# DAC.net
KiCad netlist of a schematic drawn in Altium Designer
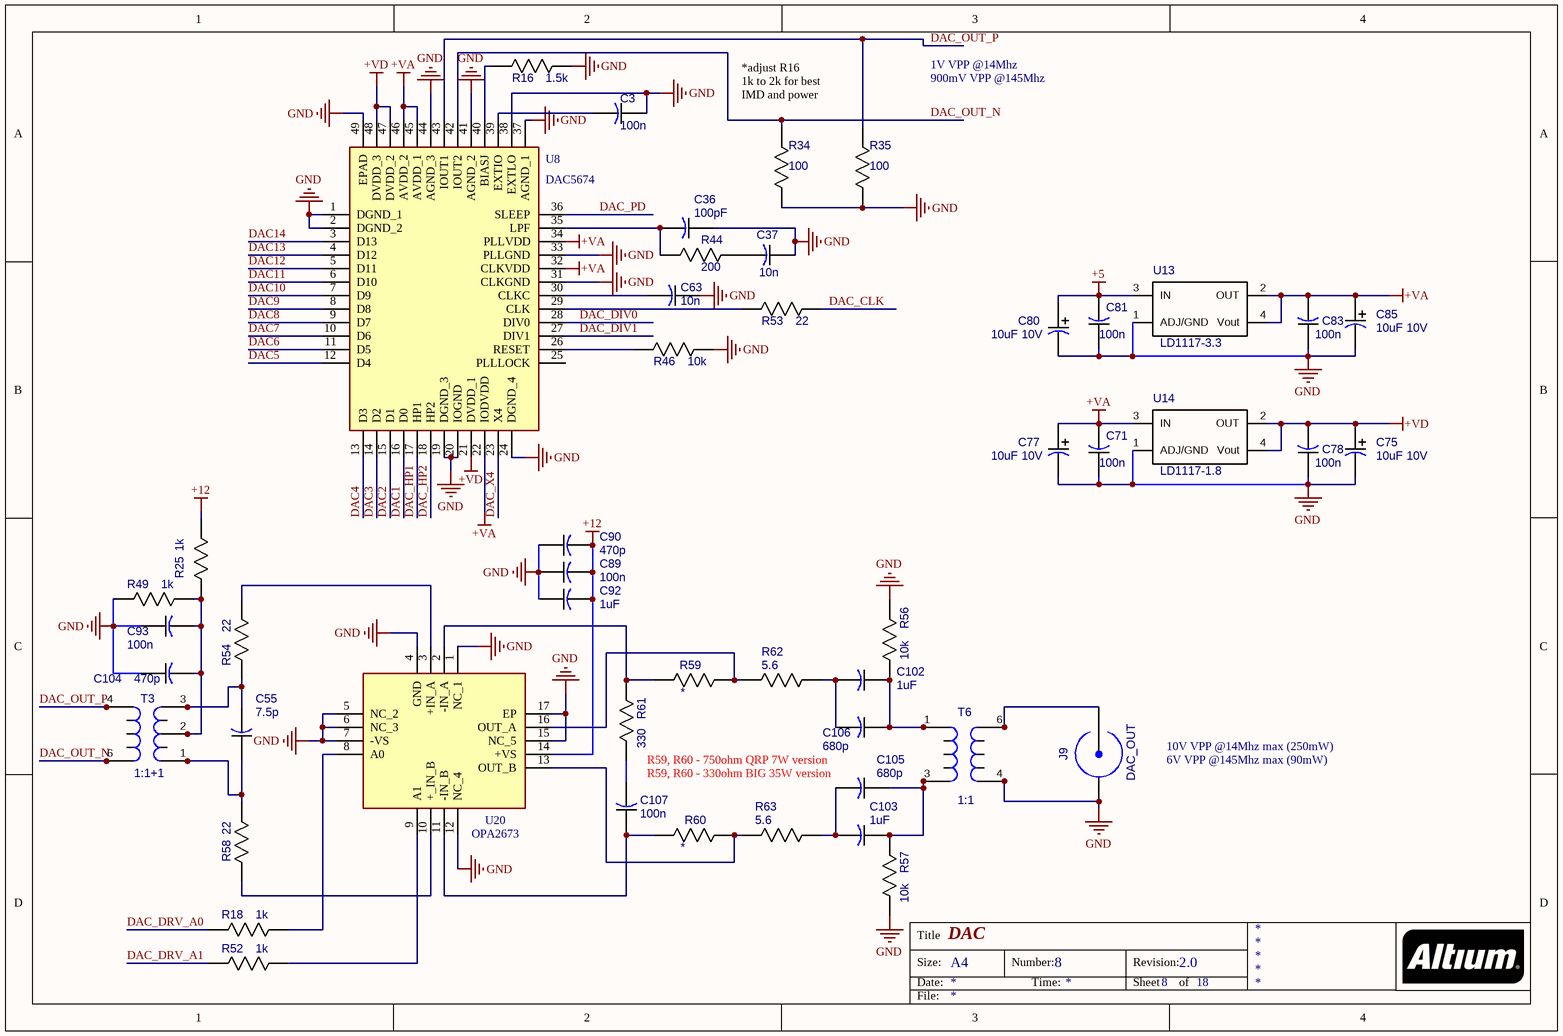
[diagram p0: DAC.SchDoc]

(export (version "E")
  (design (tool "Eeschema 10.0.6"))
  (components
    (comp (ref "C3")
      (value "100n")
      (footprint "CAP_0805")
      (description "CAP_0805")
      (libsource (lib "*") (part "CAP_0805"))
    )
    (comp (ref "C36")
      (value "100pF")
      (footprint "CAP_0805")
      (description "CAP_0805")
      (libsource (lib "*") (part "CAP_0805"))
    )
    (comp (ref "C37")
      (value "10n")
      (footprint "CAP_0805")
      (description "CAP_0805")
      (libsource (lib "*") (part "CAP_0805"))
    )
    (comp (ref "C55")
      (value "7.5p")
      (footprint "CAP_0805")
      (description "CAP_0805")
      (libsource (lib "*") (part "CAP_0805"))
    )
    (comp (ref "C63")
      (value "10n")
      (footprint "CAP_0805")
      (description "CAP_0805")
      (libsource (lib "*") (part "CAP_0805"))
    )
    (comp (ref "C71")
      (value "100n")
      (footprint "CAP_0805")
      (description "CAP_0805")
      (libsource (lib "*") (part "CAP_0805"))
    )
    (comp (ref "C75")
      (value "10uF 10V")
      (footprint "CAPAE_4.3x4.3h5.4")
      (description "CAPAE_4.3x4.3h5.4")
      (libsource (lib "MOTHERBOARD") (part "CAPAE_4.3x4.3h5.4"))
    )
    (comp (ref "C77")
      (value "10uF 10V")
      (footprint "CAPAE_4.3x4.3h5.4")
      (description "CAPAE_4.3x4.3h5.4")
      (libsource (lib "MOTHERBOARD") (part "CAPAE_4.3x4.3h5.4"))
    )
    (comp (ref "C78")
      (value "100n")
      (footprint "CAP_0805")
      (description "CAP_0805")
      (libsource (lib "*") (part "CAP_0805"))
    )
    (comp (ref "C80")
      (value "10uF 10V")
      (footprint "CAPAE_4.3x4.3h5.4")
      (description "CAPAE_4.3x4.3h5.4")
      (libsource (lib "MOTHERBOARD") (part "CAPAE_4.3x4.3h5.4"))
    )
    (comp (ref "C81")
      (value "100n")
      (footprint "CAP_0805")
      (description "CAP_0805")
      (libsource (lib "*") (part "CAP_0805"))
    )
    (comp (ref "C83")
      (value "100n")
      (footprint "CAP_0805")
      (description "CAP_0805")
      (libsource (lib "*") (part "CAP_0805"))
    )
    (comp (ref "C85")
      (value "10uF 10V")
      (footprint "CAPAE_4.3x4.3h5.4")
      (description "CAPAE_4.3x4.3h5.4")
      (libsource (lib "MOTHERBOARD") (part "CAPAE_4.3x4.3h5.4"))
    )
    (comp (ref "C89")
      (value "100n")
      (footprint "CAP_0805")
      (description "CAP_0805")
      (libsource (lib "*") (part "CAP_0805"))
    )
    (comp (ref "C90")
      (value "470p")
      (footprint "CAP_0805")
      (description "CAP_0805")
      (libsource (lib "*") (part "CAP_0805"))
    )
    (comp (ref "C92")
      (value "1uF")
      (footprint "CAP_0805")
      (description "CAP_0805")
      (libsource (lib "*") (part "CAP_0805"))
    )
    (comp (ref "C93")
      (value "100n")
      (footprint "CAP_0805")
      (description "CAP_0805")
      (libsource (lib "*") (part "CAP_0805"))
    )
    (comp (ref "C102")
      (value "1uF")
      (footprint "CAP_1206")
      (description "CAP_1206")
      (libsource (lib "*") (part "CAP_1206"))
    )
    (comp (ref "C103")
      (value "1uF")
      (footprint "CAP_1206")
      (description "CAP_1206")
      (libsource (lib "*") (part "CAP_1206"))
    )
    (comp (ref "C104")
      (value "470p")
      (footprint "CAP_0805")
      (description "CAP_0805")
      (libsource (lib "*") (part "CAP_0805"))
    )
    (comp (ref "C105")
      (value "680p")
      (footprint "CAP_1206")
      (description "CAP_1206")
      (libsource (lib "*") (part "CAP_1206"))
    )
    (comp (ref "C106")
      (value "680p")
      (footprint "CAP_1206")
      (description "CAP_1206")
      (libsource (lib "*") (part "CAP_1206"))
    )
    (comp (ref "C107")
      (value "100n")
      (footprint "CAP_0805")
      (description "CAP_0805")
      (libsource (lib "*") (part "CAP_0805"))
    )
    (comp (ref "J9")
      (value "DAC_OUT")
      (footprint "31-5431")
      (description "SMA")
      (libsource (lib "RF-UNIT_1") (part "31-5431"))
    )
    (comp (ref "R16")
      (value "1.5k")
      (footprint "RES_0805")
      (description "RES_0805")
      (libsource (lib "*") (part "RES_0805"))
    )
    (comp (ref "R18")
      (value "1k")
      (footprint "RES_0805")
      (description "RES_0805")
      (libsource (lib "*") (part "RES_0805"))
    )
    (comp (ref "R25")
      (value "1k")
      (footprint "RES_0805")
      (description "RES_0805")
      (libsource (lib "*") (part "RES_0805"))
    )
    (comp (ref "R34")
      (value "100")
      (footprint "RES_0805")
      (description "RES_0805")
      (libsource (lib "*") (part "RES_0805"))
    )
    (comp (ref "R35")
      (value "100")
      (footprint "RES_0805")
      (description "RES_0805")
      (libsource (lib "*") (part "RES_0805"))
    )
    (comp (ref "R44")
      (value "200")
      (footprint "RES_0805")
      (description "RES_0805")
      (libsource (lib "*") (part "RES_0805"))
    )
    (comp (ref "R46")
      (value "10k")
      (footprint "RES_0805")
      (description "RES_0805")
      (libsource (lib "*") (part "RES_0805"))
    )
    (comp (ref "R49")
      (value "1k")
      (footprint "RES_0805")
      (description "RES_0805")
      (libsource (lib "*") (part "RES_0805"))
    )
    (comp (ref "R52")
      (value "1k")
      (footprint "RES_0805")
      (description "RES_0805")
      (libsource (lib "*") (part "RES_0805"))
    )
    (comp (ref "R53")
      (value "22")
      (footprint "RES_0805")
      (description "RES_0805")
      (libsource (lib "*") (part "RES_0805"))
    )
    (comp (ref "R54")
      (value "22")
      (footprint "RES_0805")
      (description "RES_0805")
      (libsource (lib "*") (part "RES_0805"))
    )
    (comp (ref "R56")
      (value "10k")
      (footprint "RES_0805")
      (description "RES_0805")
      (libsource (lib "*") (part "RES_0805"))
    )
    (comp (ref "R57")
      (value "10k")
      (footprint "RES_0805")
      (description "RES_0805")
      (libsource (lib "*") (part "RES_0805"))
    )
    (comp (ref "R58")
      (value "22")
      (footprint "RES_0805")
      (description "RES_0805")
      (libsource (lib "*") (part "RES_0805"))
    )
    (comp (ref "R59")
      (value "*")
      (footprint "RES_0805")
      (description "RES_0805")
      (libsource (lib "*") (part "RES_0805"))
    )
    (comp (ref "R60")
      (value "*")
      (footprint "RES_0805")
      (description "RES_0805")
      (libsource (lib "*") (part "RES_0805"))
    )
    (comp (ref "R61")
      (value "330")
      (footprint "RES_0805")
      (description "RES_0805")
      (libsource (lib "*") (part "RES_0805"))
    )
    (comp (ref "R62")
      (value "5.6")
      (footprint "RES_1206")
      (description "RES_1206")
      (libsource (lib "*") (part "RES_1206"))
    )
    (comp (ref "R63")
      (value "5.6")
      (footprint "RES_1206")
      (description "RES_1206")
      (libsource (lib "*") (part "RES_1206"))
    )
    (comp (ref "T3")
      (value "1:1+1")
      (footprint "TRANSF_ACORE2")
      (description "Transformer")
      (libsource (lib "MOTHERBOARD_1") (part "TRANSF_ACORE2"))
    )
    (comp (ref "T6")
      (value "1:1")
      (footprint "TRANSF_ACORE")
      (description "Transformer")
      (libsource (lib "MOTHERBOARD_1") (part "TRANSF_ACORE"))
    )
    (comp (ref "U8")
      (value "DAC5674")
      (footprint "SamacSys:QFP50P900X900X100-49N")
      (description "Integrated Circuit")
      (fields (field (name "MANUFACTURER_PART_NUMBER") "DAC5674IPHP"))
      (libsource (lib "*") (part "DAC5674IPHP"))
    )
    (comp (ref "U13")
      (value "LD1117-3.3")
      (footprint "LT1117CST-3.3")
      (description "LT1117CST-3.3")
      (fields (field (name "Comment") "1117-3.3"))
      (libsource (lib "*") (part "LT1117CST-3.3"))
    )
    (comp (ref "U14")
      (value "LD1117-1.8")
      (footprint "LT1117CST-3.3")
      (description "LT1117CST-1.8")
      (fields (field (name "Comment") "1117-1.8"))
      (libsource (lib "*") (part "LT1117CST-3.3"))
    )
    (comp (ref "U20")
      (value "OPA2673")
      (footprint "SamacSys:QFN65P400X400X100-17N-D")
      (description "Integrated Circuit")
      (fields
        (field (name "MANUFACTURER_PART_NUMBER") "OPA2673IRGVT")
        (field (name "MOUSER PART NUMBER") "595-OPA2673IRGVT")
      )
      (libsource (lib "*") (part "OPA2673IRGVT"))
    )
  )
  (nets
    (net (code "1") (name "+5") (class "Default")
      (node (ref "C80") (pin "1") (pinfunction "PLUS_1") (pintype "passive"))
      (node (ref "C81") (pin "2") (pinfunction "2_2") (pintype "passive"))
      (node (ref "U13") (pin "3") (pinfunction "IN_3") (pintype "passive"))
    )
    (net (code "2") (name "+12") (class "Default")
      (node (ref "C89") (pin "2") (pinfunction "2_2") (pintype "passive"))
      (node (ref "C90") (pin "2") (pinfunction "2_2") (pintype "passive"))
      (node (ref "C92") (pin "2") (pinfunction "2_2") (pintype "passive"))
      (node (ref "R25") (pin "2") (pinfunction "2_2") (pintype "passive"))
      (node (ref "U20") (pin "14") (pinfunction "+VS_14") (pintype "passive"))
    )
    (net (code "3") (name "+VA") (class "Default")
      (node (ref "C71") (pin "2") (pinfunction "2_2") (pintype "passive"))
      (node (ref "C77") (pin "1") (pinfunction "PLUS_1") (pintype "passive"))
      (node (ref "C83") (pin "2") (pinfunction "2_2") (pintype "passive"))
      (node (ref "C85") (pin "1") (pinfunction "PLUS_1") (pintype "passive"))
      (node (ref "U13") (pin "2") (pinfunction "OUT_2") (pintype "passive"))
      (node (ref "U13") (pin "4") (pinfunction "Vout_4") (pintype "passive"))
      (node (ref "U14") (pin "3") (pinfunction "IN_3") (pintype "passive"))
      (node (ref "U8") (pin "22") (pinfunction "IODVDD_22") (pintype "passive"))
      (node (ref "U8") (pin "32") (pinfunction "CLKVDD_32") (pintype "passive"))
      (node (ref "U8") (pin "34") (pinfunction "PLLVDD_34") (pintype "passive"))
      (node (ref "U8") (pin "45") (pinfunction "AVDD_1_45") (pintype "passive"))
      (node (ref "U8") (pin "46") (pinfunction "AVDD_2_46") (pintype "passive"))
    )
    (net (code "4") (name "+VD") (class "Default")
      (node (ref "C75") (pin "1") (pinfunction "PLUS_1") (pintype "passive"))
      (node (ref "C78") (pin "2") (pinfunction "2_2") (pintype "passive"))
      (node (ref "U14") (pin "2") (pinfunction "OUT_2") (pintype "passive"))
      (node (ref "U14") (pin "4") (pinfunction "Vout_4") (pintype "passive"))
      (node (ref "U8") (pin "21") (pinfunction "DVDD_1_21") (pintype "passive"))
      (node (ref "U8") (pin "47") (pinfunction "DVDD_2_47") (pintype "passive"))
      (node (ref "U8") (pin "48") (pinfunction "DVDD_3_48") (pintype "passive"))
    )
    (net (code "5") (name "/DAC1") (class "Default")
      (node (ref "U8") (pin "16") (pinfunction "D0_16") (pintype "passive"))
    )
    (net (code "6") (name "/DAC2") (class "Default")
      (node (ref "U8") (pin "15") (pinfunction "D1_15") (pintype "passive"))
    )
    (net (code "7") (name "/DAC3") (class "Default")
      (node (ref "U8") (pin "14") (pinfunction "D2_14") (pintype "passive"))
    )
    (net (code "8") (name "/DAC4") (class "Default")
      (node (ref "U8") (pin "13") (pinfunction "D3_13") (pintype "passive"))
    )
    (net (code "9") (name "/DAC5") (class "Default")
      (node (ref "U8") (pin "12") (pinfunction "D4_12") (pintype "passive"))
    )
    (net (code "10") (name "/DAC6") (class "Default")
      (node (ref "U8") (pin "11") (pinfunction "D5_11") (pintype "passive"))
    )
    (net (code "11") (name "/DAC7") (class "Default")
      (node (ref "U8") (pin "10") (pinfunction "D6_10") (pintype "passive"))
    )
    (net (code "12") (name "/DAC8") (class "Default")
      (node (ref "U8") (pin "9") (pinfunction "D7_9") (pintype "passive"))
    )
    (net (code "13") (name "/DAC9") (class "Default")
      (node (ref "U8") (pin "8") (pinfunction "D8_8") (pintype "passive"))
    )
    (net (code "14") (name "/DAC10") (class "Default")
      (node (ref "U8") (pin "7") (pinfunction "D9_7") (pintype "passive"))
    )
    (net (code "15") (name "/DAC11") (class "Default")
      (node (ref "U8") (pin "6") (pinfunction "D10_6") (pintype "passive"))
    )
    (net (code "16") (name "/DAC12") (class "Default")
      (node (ref "U8") (pin "5") (pinfunction "D11_5") (pintype "passive"))
    )
    (net (code "17") (name "/DAC13") (class "Default")
      (node (ref "U8") (pin "4") (pinfunction "D12_4") (pintype "passive"))
    )
    (net (code "18") (name "/DAC14") (class "Default")
      (node (ref "U8") (pin "3") (pinfunction "D13_3") (pintype "passive"))
    )
    (net (code "19") (name "/DAC_CLK") (class "Default")
      (node (ref "R53") (pin "1") (pinfunction "1_1") (pintype "passive"))
    )
    (net (code "20") (name "/DAC_DIV0") (class "Default")
      (node (ref "U8") (pin "28") (pinfunction "DIV0_28") (pintype "passive"))
    )
    (net (code "21") (name "/DAC_DIV1") (class "Default")
      (node (ref "U8") (pin "27") (pinfunction "DIV1_27") (pintype "passive"))
    )
    (net (code "22") (name "/DAC_DRV_A0") (class "Default")
      (node (ref "R18") (pin "1") (pinfunction "1_1") (pintype "passive"))
    )
    (net (code "23") (name "/DAC_DRV_A1") (class "Default")
      (node (ref "R52") (pin "1") (pinfunction "1_1") (pintype "passive"))
    )
    (net (code "24") (name "/DAC_HP1") (class "Default")
      (node (ref "U8") (pin "17") (pinfunction "HP1_17") (pintype "passive"))
    )
    (net (code "25") (name "/DAC_HP2") (class "Default")
      (node (ref "U8") (pin "18") (pinfunction "HP2_18") (pintype "passive"))
    )
    (net (code "26") (name "/DAC_OUT_N") (class "Default")
      (node (ref "R34") (pin "2") (pinfunction "2_2") (pintype "passive"))
      (node (ref "T3") (pin "10") (pinfunction "0_10") (pintype "passive"))
      (node (ref "T3") (pin "6") (pinfunction "P2_6") (pintype "passive"))
      (node (ref "U8") (pin "42") (pinfunction "IOUT2_42") (pintype "passive"))
    )
    (net (code "27") (name "/DAC_OUT_P") (class "Default")
      (node (ref "R35") (pin "2") (pinfunction "2_2") (pintype "passive"))
      (node (ref "T3") (pin "11") (pinfunction "0_11") (pintype "passive"))
      (node (ref "T3") (pin "4") (pinfunction "P1_4") (pintype "passive"))
      (node (ref "U8") (pin "43") (pinfunction "IOUT1_43") (pintype "passive"))
    )
    (net (code "28") (name "/DAC_PD") (class "Default")
      (node (ref "U8") (pin "36") (pinfunction "SLEEP_36") (pintype "passive"))
    )
    (net (code "29") (name "/DAC_X4") (class "Default")
      (node (ref "U8") (pin "23") (pinfunction "X4_23") (pintype "passive"))
    )
    (net (code "30") (name "GND") (class "Default")
      (node (ref "C104") (pin "1") (pinfunction "1_1") (pintype "passive"))
      (node (ref "C3") (pin "1") (pinfunction "1_1") (pintype "passive"))
      (node (ref "C36") (pin "1") (pinfunction "1_1") (pintype "passive"))
      (node (ref "C37") (pin "1") (pinfunction "1_1") (pintype "passive"))
      (node (ref "C63") (pin "1") (pinfunction "1_1") (pintype "passive"))
      (node (ref "C71") (pin "1") (pinfunction "1_1") (pintype "passive"))
      (node (ref "C75") (pin "2") (pinfunction "MINUS_2") (pintype "passive"))
      (node (ref "C77") (pin "2") (pinfunction "MINUS_2") (pintype "passive"))
      (node (ref "C78") (pin "1") (pinfunction "1_1") (pintype "passive"))
      (node (ref "C80") (pin "2") (pinfunction "MINUS_2") (pintype "passive"))
      (node (ref "C81") (pin "1") (pinfunction "1_1") (pintype "passive"))
      (node (ref "C83") (pin "1") (pinfunction "1_1") (pintype "passive"))
      (node (ref "C85") (pin "2") (pinfunction "MINUS_2") (pintype "passive"))
      (node (ref "C89") (pin "1") (pinfunction "1_1") (pintype "passive"))
      (node (ref "C90") (pin "1") (pinfunction "1_1") (pintype "passive"))
      (node (ref "C92") (pin "1") (pinfunction "1_1") (pintype "passive"))
      (node (ref "C93") (pin "1") (pinfunction "1_1") (pintype "passive"))
      (node (ref "J9") (pin "1") (pinfunction "GND_1") (pintype "passive"))
      (node (ref "J9") (pin "2") (pinfunction "GND_2") (pintype "passive"))
      (node (ref "J9") (pin "3") (pinfunction "GND_3") (pintype "passive"))
      (node (ref "J9") (pin "4") (pinfunction "GND_4") (pintype "passive"))
      (node (ref "R16") (pin "1") (pinfunction "1_1") (pintype "passive"))
      (node (ref "R34") (pin "1") (pinfunction "1_1") (pintype "passive"))
      (node (ref "R35") (pin "1") (pinfunction "1_1") (pintype "passive"))
      (node (ref "R46") (pin "1") (pinfunction "1_1") (pintype "passive"))
      (node (ref "R49") (pin "2") (pinfunction "2_2") (pintype "passive"))
      (node (ref "R56") (pin "1") (pinfunction "1_1") (pintype "passive"))
      (node (ref "R57") (pin "2") (pinfunction "2_2") (pintype "passive"))
      (node (ref "T6") (pin "11") (pinfunction "0_11") (pintype "passive"))
      (node (ref "T6") (pin "4") (pinfunction "S2_4") (pintype "passive"))
      (node (ref "U13") (pin "1") (pinfunction "ADJ/GND_1") (pintype "passive"))
      (node (ref "U14") (pin "1") (pinfunction "ADJ/GND_1") (pintype "passive"))
      (node (ref "U20") (pin "1") (pinfunction "NC_1_1") (pintype "passive"))
      (node (ref "U20") (pin "12") (pinfunction "NC_4_12") (pintype "passive"))
      (node (ref "U20") (pin "15") (pinfunction "NC_5_15") (pintype "passive"))
      (node (ref "U20") (pin "17") (pinfunction "EP_17") (pintype "passive"))
      (node (ref "U20") (pin "4") (pinfunction "GND_4") (pintype "passive"))
      (node (ref "U20") (pin "5") (pinfunction "NC_2_5") (pintype "passive"))
      (node (ref "U20") (pin "6") (pinfunction "NC_3_6") (pintype "passive"))
      (node (ref "U20") (pin "7") (pinfunction "-VS_7") (pintype "passive"))
      (node (ref "U8") (pin "1") (pinfunction "DGND_1_1") (pintype "passive"))
      (node (ref "U8") (pin "19") (pinfunction "DGND_3_19") (pintype "passive"))
      (node (ref "U8") (pin "2") (pinfunction "DGND_2_2") (pintype "passive"))
      (node (ref "U8") (pin "20") (pinfunction "IOGND_20") (pintype "passive"))
      (node (ref "U8") (pin "24") (pinfunction "DGND_4_24") (pintype "passive"))
      (node (ref "U8") (pin "31") (pinfunction "CLKGND_31") (pintype "passive"))
      (node (ref "U8") (pin "33") (pinfunction "PLLGND_33") (pintype "passive"))
      (node (ref "U8") (pin "37") (pinfunction "AGND_1_37") (pintype "passive"))
      (node (ref "U8") (pin "38") (pinfunction "EXTLO_38") (pintype "passive"))
      (node (ref "U8") (pin "41") (pinfunction "AGND_2_41") (pintype "passive"))
      (node (ref "U8") (pin "44") (pinfunction "AGND_3_44") (pintype "passive"))
      (node (ref "U8") (pin "49") (pinfunction "EPAD_49") (pintype "passive"))
    )
    (net (code "31") (name "Net-(C37-Pad2)") (class "Default")
      (node (ref "C37") (pin "2") (pinfunction "2_2") (pintype "passive"))
      (node (ref "R44") (pin "1") (pinfunction "1_1") (pintype "passive"))
    )
    (net (code "32") (name "Net-(C102-Pad2)") (class "Default")
      (node (ref "C102") (pin "2") (pinfunction "2_2") (pintype "passive"))
      (node (ref "C106") (pin "2") (pinfunction "2_2") (pintype "passive"))
      (node (ref "R62") (pin "1") (pinfunction "1_1") (pintype "passive"))
    )
    (net (code "33") (name "Net-(C103-Pad2)") (class "Default")
      (node (ref "C103") (pin "2") (pinfunction "2_2") (pintype "passive"))
      (node (ref "C105") (pin "2") (pinfunction "2_2") (pintype "passive"))
      (node (ref "R63") (pin "1") (pinfunction "1_1") (pintype "passive"))
    )
    (net (code "34") (name "Net-(C107-Pad2)") (class "Default")
      (node (ref "C107") (pin "2") (pinfunction "2_2") (pintype "passive"))
      (node (ref "R61") (pin "2") (pinfunction "2_2") (pintype "passive"))
    )
    (net (code "35") (name "Net-(J9-CON)") (class "Default")
      (node (ref "J9") (pin "5") (pinfunction "CON_5") (pintype "passive"))
      (node (ref "T6") (pin "10") (pinfunction "0_10") (pintype "passive"))
      (node (ref "T6") (pin "6") (pinfunction "S1_6") (pintype "passive"))
    )
    (net (code "36") (name "Net-(T3-S1)") (class "Default")
      (node (ref "C55") (pin "2") (pinfunction "2_2") (pintype "passive"))
      (node (ref "R54") (pin "1") (pinfunction "1_1") (pintype "passive"))
      (node (ref "T3") (pin "3") (pinfunction "S1_3") (pintype "passive"))
      (node (ref "T3") (pin "9") (pinfunction "0_9") (pintype "passive"))
    )
    (net (code "37") (name "Net-(T3-S2)") (class "Default")
      (node (ref "C104") (pin "2") (pinfunction "2_2") (pintype "passive"))
      (node (ref "C93") (pin "2") (pinfunction "2_2") (pintype "passive"))
      (node (ref "R25") (pin "1") (pinfunction "1_1") (pintype "passive"))
      (node (ref "R49") (pin "1") (pinfunction "1_1") (pintype "passive"))
      (node (ref "T3") (pin "2") (pinfunction "S2_2") (pintype "passive"))
      (node (ref "T3") (pin "8") (pinfunction "0_8") (pintype "passive"))
    )
    (net (code "38") (name "Net-(T3-S3)") (class "Default")
      (node (ref "C55") (pin "1") (pinfunction "1_1") (pintype "passive"))
      (node (ref "R58") (pin "2") (pinfunction "2_2") (pintype "passive"))
      (node (ref "T3") (pin "1") (pinfunction "S3_1") (pintype "passive"))
      (node (ref "T3") (pin "7") (pinfunction "0_7") (pintype "passive"))
    )
    (net (code "39") (name "Net-(T6-P1)") (class "Default")
      (node (ref "C102") (pin "1") (pinfunction "1_1") (pintype "passive"))
      (node (ref "C106") (pin "1") (pinfunction "1_1") (pintype "passive"))
      (node (ref "R56") (pin "2") (pinfunction "2_2") (pintype "passive"))
      (node (ref "T6") (pin "1") (pinfunction "P1_1") (pintype "passive"))
      (node (ref "T6") (pin "7") (pinfunction "0_7") (pintype "passive"))
    )
    (net (code "40") (name "Net-(T6-P2)") (class "Default")
      (node (ref "C103") (pin "1") (pinfunction "1_1") (pintype "passive"))
      (node (ref "C105") (pin "1") (pinfunction "1_1") (pintype "passive"))
      (node (ref "R57") (pin "1") (pinfunction "1_1") (pintype "passive"))
      (node (ref "T6") (pin "3") (pinfunction "P2_3") (pintype "passive"))
      (node (ref "T6") (pin "9") (pinfunction "0_9") (pintype "passive"))
    )
    (net (code "41") (name "Net-(U8-BIASJ)") (class "Default")
      (node (ref "R16") (pin "2") (pinfunction "2_2") (pintype "passive"))
      (node (ref "U8") (pin "40") (pinfunction "BIASJ_40") (pintype "passive"))
    )
    (net (code "42") (name "Net-(U8-CLK)") (class "Default")
      (node (ref "R53") (pin "2") (pinfunction "2_2") (pintype "passive"))
      (node (ref "U8") (pin "29") (pinfunction "CLK_29") (pintype "passive"))
    )
    (net (code "43") (name "Net-(U8-CLKC)") (class "Default")
      (node (ref "C63") (pin "2") (pinfunction "2_2") (pintype "passive"))
      (node (ref "U8") (pin "30") (pinfunction "CLKC_30") (pintype "passive"))
    )
    (net (code "44") (name "Net-(U8-EXTIO)") (class "Default")
      (node (ref "C3") (pin "2") (pinfunction "2_2") (pintype "passive"))
      (node (ref "U8") (pin "39") (pinfunction "EXTIO_39") (pintype "passive"))
    )
    (net (code "45") (name "Net-(U8-LPF)") (class "Default")
      (node (ref "C36") (pin "2") (pinfunction "2_2") (pintype "passive"))
      (node (ref "R44") (pin "2") (pinfunction "2_2") (pintype "passive"))
      (node (ref "U8") (pin "35") (pinfunction "LPF_35") (pintype "passive"))
    )
    (net (code "46") (name "Net-(U8-RESET)") (class "Default")
      (node (ref "R46") (pin "2") (pinfunction "2_2") (pintype "passive"))
      (node (ref "U8") (pin "26") (pinfunction "RESET_26") (pintype "passive"))
    )
    (net (code "47") (name "Net-(U20-+IN_A)") (class "Default")
      (node (ref "R54") (pin "2") (pinfunction "2_2") (pintype "passive"))
      (node (ref "U20") (pin "3") (pinfunction "+IN_A_3") (pintype "passive"))
    )
    (net (code "48") (name "Net-(U20-+_IN_B)") (class "Default")
      (node (ref "R58") (pin "1") (pinfunction "1_1") (pintype "passive"))
      (node (ref "U20") (pin "10") (pinfunction "+_IN_B_10") (pintype "passive"))
    )
    (net (code "49") (name "Net-(U20--IN_A)") (class "Default")
      (node (ref "R59") (pin "2") (pinfunction "2_2") (pintype "passive"))
      (node (ref "R61") (pin "1") (pinfunction "1_1") (pintype "passive"))
      (node (ref "U20") (pin "2") (pinfunction "-IN_A_2") (pintype "passive"))
    )
    (net (code "50") (name "Net-(U20--IN_B)") (class "Default")
      (node (ref "C107") (pin "1") (pinfunction "1_1") (pintype "passive"))
      (node (ref "R60") (pin "2") (pinfunction "2_2") (pintype "passive"))
      (node (ref "U20") (pin "11") (pinfunction "-IN_B_11") (pintype "passive"))
    )
    (net (code "51") (name "Net-(U20-A0)") (class "Default")
      (node (ref "R18") (pin "2") (pinfunction "2_2") (pintype "passive"))
      (node (ref "U20") (pin "8") (pinfunction "A0_8") (pintype "passive"))
    )
    (net (code "52") (name "Net-(U20-A1)") (class "Default")
      (node (ref "R52") (pin "2") (pinfunction "2_2") (pintype "passive"))
      (node (ref "U20") (pin "9") (pinfunction "A1_9") (pintype "passive"))
    )
    (net (code "53") (name "Net-(U20-OUT_A)") (class "Default")
      (node (ref "R59") (pin "1") (pinfunction "1_1") (pintype "passive"))
      (node (ref "R62") (pin "2") (pinfunction "2_2") (pintype "passive"))
      (node (ref "U20") (pin "16") (pinfunction "OUT_A_16") (pintype "passive"))
    )
    (net (code "54") (name "Net-(U20-OUT_B)") (class "Default")
      (node (ref "R60") (pin "1") (pinfunction "1_1") (pintype "passive"))
      (node (ref "R63") (pin "2") (pinfunction "2_2") (pintype "passive"))
      (node (ref "U20") (pin "13") (pinfunction "OUT_B_13") (pintype "passive"))
    )
    (net (code "55") (name "unconnected-(T6-0-Pad8)") (class "Default")
      (node (ref "T6") (pin "8") (pinfunction "0_8") (pintype "passive"))
    )
    (net (code "56") (name "unconnected-(U8-PLLLOCK-Pad25)") (class "Default")
      (node (ref "U8") (pin "25") (pinfunction "PLLLOCK_25") (pintype "passive"))
    )
  )
)
